# Temp_recorder_SAMD21.net
KiCad netlist of a schematic drawn in Altium Designer
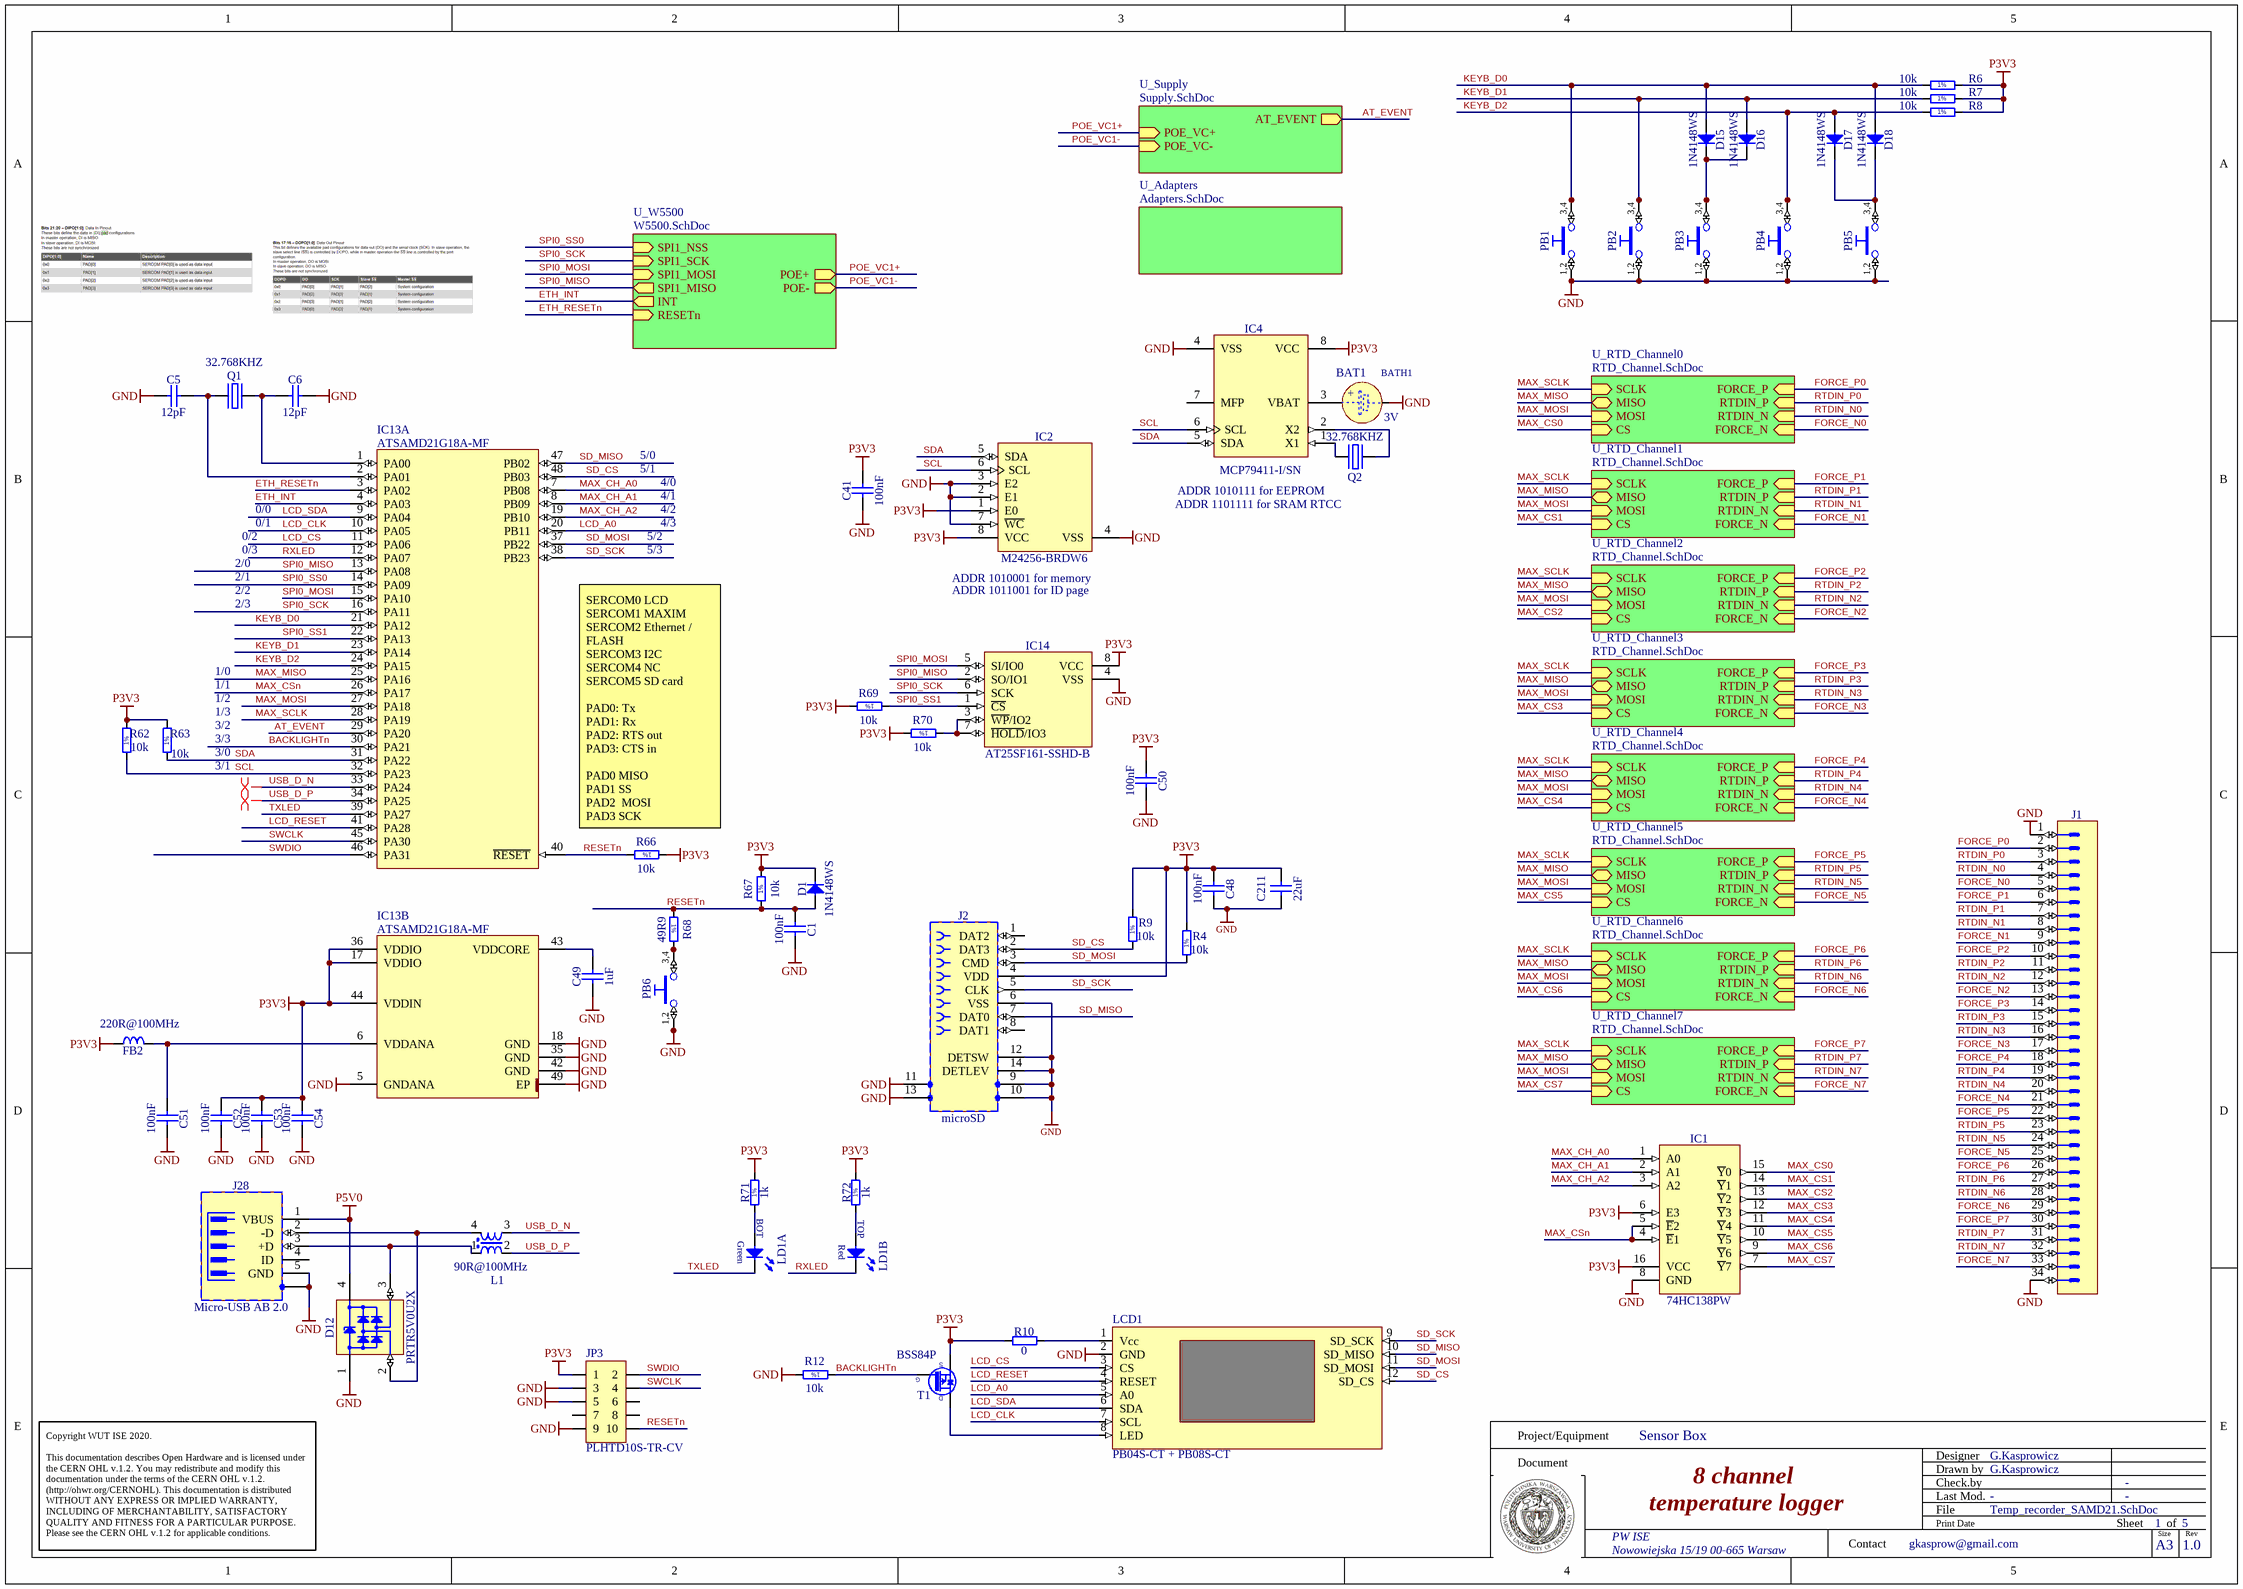
[diagram p0: Temp_recorder_SAMD21.SchDoc]

(export (version "E")
  (design (tool "Eeschema 10.0.6"))
  (components
    (comp (ref "BAT1")
      (value "3V")
      (footprint "BAT_VARTA_CR1220")
      (description "Battery for use only with Socket Holder")
      (fields
        (field (name "PART NUMBER") "BAT_VARTA_CR1220")
        (field (name "POWER") "35mAh")
        (field (name "AUTHOR") "CERN DEM JLC")
      )
      (libsource (lib "Eletro-mechanical") (part "Battery No Pin"))
    )
    (comp (ref "BATH1")
      (value "~")
      (footprint "BATH_KEYSTONE_3000")
      (description "Battery Holder whit 2 Pin")
      (fields
        (field (name "PART NUMBER") "BATH_KEYSTONE_3000")
        (field (name "MANUFACTURER") "KEYSTONE")
        (field (name "AUTHOR") "CERN DEM JLC")
      )
      (libsource (lib "Eletro-mechanical") (part "Battery Holder 2 Pin"))
    )
    (comp (ref "C1")
      (value "100nF")
      (footprint "CAPC1005X55N")
      (description "Non-polarised capacitor")
      (fields
        (field (name "PART NUMBER") "CC0402_100NF_16V_10%_X7R")
        (field (name "VOLTAGE") "16V")
        (field (name "AUTHOR") "CERN DEM JLC")
      )
      (libsource (lib "Capacitors") (part "Capacitor - non polarized"))
    )
    (comp (ref "C5")
      (value "12pF")
      (footprint "CAPC1005X55N")
      (description "Non-polarised capacitor")
      (fields
        (field (name "PART NUMBER") "CC0402_12PF_50V_5%_C0G")
        (field (name "VOLTAGE") "50V")
        (field (name "AUTHOR") "CERN DEM JLC")
      )
      (libsource (lib "Capacitors") (part "Capacitor - non polarized"))
    )
    (comp (ref "C6")
      (value "12pF")
      (footprint "CAPC1005X55N")
      (description "Non-polarised capacitor")
      (fields
        (field (name "PART NUMBER") "CC0402_12PF_50V_5%_C0G")
        (field (name "VOLTAGE") "50V")
        (field (name "AUTHOR") "CERN DEM JLC")
      )
      (libsource (lib "Capacitors") (part "Capacitor - non polarized"))
    )
    (comp (ref "C41")
      (value "100nF")
      (footprint "CAPC1005X55N")
      (description "Non-polarised capacitor")
      (fields
        (field (name "PART NUMBER") "CC0402_100NF_16V_10%_X5R")
        (field (name "VOLTAGE") "16V")
        (field (name "AUTHOR") "CERN DEM JLC")
      )
      (libsource (lib "Capacitors") (part "Capacitor - non polarized"))
    )
    (comp (ref "C48")
      (value "100nF")
      (footprint "CAPC1005X55N")
      (description "Non-polarised capacitor")
      (fields
        (field (name "PART NUMBER") "CC0402_100NF_16V_10%_X7R")
        (field (name "VOLTAGE") "16V")
        (field (name "AUTHOR") "CERN DEM JLC")
      )
      (libsource (lib "Capacitors") (part "Capacitor - non polarized"))
    )
    (comp (ref "C49")
      (value "1uF")
      (footprint "CAPC1608X87N")
      (description "Non-polarised capacitor")
      (fields
        (field (name "PART NUMBER") "CC0603_1UF_16V_10%_X7R")
        (field (name "VOLTAGE") "16V")
        (field (name "AUTHOR") "CERN DEM JLC")
      )
      (libsource (lib "Capacitors") (part "Capacitor - non polarized"))
    )
    (comp (ref "C50")
      (value "100nF")
      (footprint "CAPC1005X55N")
      (description "Non-polarised capacitor")
      (fields
        (field (name "PART NUMBER") "CC0402_100NF_16V_10%_X7R")
        (field (name "VOLTAGE") "16V")
        (field (name "AUTHOR") "CERN DEM JLC")
      )
      (libsource (lib "Capacitors") (part "Capacitor - non polarized"))
    )
    (comp (ref "C51")
      (value "100nF")
      (footprint "CAPC1005X55N")
      (description "Non-polarised capacitor")
      (fields
        (field (name "PART NUMBER") "CC0402_100NF_16V_10%_X7R")
        (field (name "VOLTAGE") "16V")
        (field (name "AUTHOR") "CERN DEM JLC")
      )
      (libsource (lib "Capacitors") (part "Capacitor - non polarized"))
    )
    (comp (ref "C52")
      (value "100nF")
      (footprint "CAPC1005X55N")
      (description "Non-polarised capacitor")
      (fields
        (field (name "PART NUMBER") "CC0402_100NF_16V_10%_X7R")
        (field (name "VOLTAGE") "16V")
        (field (name "AUTHOR") "CERN DEM JLC")
      )
      (libsource (lib "Capacitors") (part "Capacitor - non polarized"))
    )
    (comp (ref "C53")
      (value "100nF")
      (footprint "CAPC1005X55N")
      (description "Non-polarised capacitor")
      (fields
        (field (name "PART NUMBER") "CC0402_100NF_16V_10%_X7R")
        (field (name "VOLTAGE") "16V")
        (field (name "AUTHOR") "CERN DEM JLC")
      )
      (libsource (lib "Capacitors") (part "Capacitor - non polarized"))
    )
    (comp (ref "C54")
      (value "100nF")
      (footprint "CAPC1005X55N")
      (description "Non-polarised capacitor")
      (fields
        (field (name "PART NUMBER") "CC0402_100NF_16V_10%_X7R")
        (field (name "VOLTAGE") "16V")
        (field (name "AUTHOR") "CERN DEM JLC")
      )
      (libsource (lib "Capacitors") (part "Capacitor - non polarized"))
    )
    (comp (ref "C211")
      (value "22uF")
      (footprint "CAPC2012X135N")
      (description "Non-polarised capacitor")
      (fields
        (field (name "PART NUMBER") "CC0805_22UF_16V_10%_X5R")
        (field (name "VOLTAGE") "16V")
        (field (name "AUTHOR") "CERN DEM JLC")
      )
      (libsource (lib "Capacitors") (part "Capacitor - non polarized"))
    )
    (comp (ref "D1")
      (value "1N4148WS")
      (footprint "SODFL2512X100N")
      (description "Diode")
      (fields
        (field (name "VOLTAGE") "75V")
        (field (name "POWER") "150mA")
        (field (name "AUTHOR") "CERN DEM JLC")
      )
      (libsource (lib "ICs And Semiconductors") (part "Diode"))
    )
    (comp (ref "D12")
      (value "PRTR5V0U2X")
      (footprint "SOT190P230X110-4N")
      (description "Ultra Low Capacitance Double Rail-to-Rail ESD Protection Diode")
      (fields
        (field (name "VOLTAGE") "5.5V")
        (field (name "MANUFACTURER") "NXP SEMICONDUCTORS")
        (field (name "AUTHOR") "CERN DEM JLC")
      )
      (libsource (lib "ICs And Semiconductors") (part "PRTR5V0U2X"))
    )
    (comp (ref "D15")
      (value "1N4148WS")
      (footprint "SODFL2512X100N")
      (description "Diode")
      (fields
        (field (name "VOLTAGE") "75V")
        (field (name "POWER") "150mA")
        (field (name "AUTHOR") "CERN DEM JLC")
      )
      (libsource (lib "ICs And Semiconductors") (part "Diode"))
    )
    (comp (ref "D16")
      (value "1N4148WS")
      (footprint "SODFL2512X100N")
      (description "Diode")
      (fields
        (field (name "VOLTAGE") "75V")
        (field (name "POWER") "150mA")
        (field (name "AUTHOR") "CERN DEM JLC")
      )
      (libsource (lib "ICs And Semiconductors") (part "Diode"))
    )
    (comp (ref "D17")
      (value "1N4148WS")
      (footprint "SODFL2512X100N")
      (description "Diode")
      (fields
        (field (name "VOLTAGE") "75V")
        (field (name "POWER") "150mA")
        (field (name "AUTHOR") "CERN DEM JLC")
      )
      (libsource (lib "ICs And Semiconductors") (part "Diode"))
    )
    (comp (ref "D18")
      (value "1N4148WS")
      (footprint "SODFL2512X100N")
      (description "Diode")
      (fields
        (field (name "VOLTAGE") "75V")
        (field (name "POWER") "150mA")
        (field (name "AUTHOR") "CERN DEM JLC")
      )
      (libsource (lib "ICs And Semiconductors") (part "Diode"))
    )
    (comp (ref "FB2")
      (value "220R@100MHz")
      (footprint "INDC2012X105N")
      (description "Inductor")
      (fields
        (field (name "PART NUMBER") "IND0805_MURATA_BLM21PG221SN1D")
        (field (name "POWER") "2A")
        (field (name "AUTHOR") "CERN DEM JLC")
      )
      (libsource (lib "Inductors & Transformers") (part "Inductor"))
    )
    (comp (ref "IC1")
      (value "74HC138PW")
      (footprint "SOP65P640X110-16N")
      (description "3-Line to 8-Line Decoder/Demultiplexer")
      (fields (field (name "MANUFACTURER") "NXP SEMICONDUCTORS") (field (name "AUTHOR") "CERN DEM JLC"))
      (libsource (lib "ICs And Semiconductors") (part "74138_a"))
    )
    (comp (ref "IC2")
      (value "M24256-BRDW6")
      (footprint "SOP65P640X120-8N")
      (description "256-Kbit Serial I²C Bus EEPROM")
      (fields
        (field (name "PART NUMBER") "M24256-BRDW6P")
        (field (name "MANUFACTURER") "ST MICROELECTRONICS")
        (field (name "AUTHOR") "CERN DEM MR")
      )
      (libsource (lib "LIBRARY_SCH") (part "MEM_M24256-BRDW6P"))
    )
    (comp (ref "IC4")
      (value "MCP79411-I/SN")
      (footprint "SOIC127P600X175-8N")
      (description "I2C Real-Time Clock/Calendar with EEPROM, SRAM, Unique ID and Battery Switchover")
      (fields (field (name "MANUFACTURER") "MICROCHIP TECHNOLOGY") (field (name "AUTHOR") "GK"))
      (libsource (lib "ICs_Analog_Interfaces") (part "RTC_MCP79411"))
    )
    (comp (ref "IC13")
      (value "ATSAMD21G18A-MF")
      (footprint "QFN50P700X700X100-49N-S525")
      (fields (field (name "MANUFACTURER") "MICROCHIP") (field (name "AUTHOR") "CERN DEM BC"))
      (libsource (lib "ICs And Semiconductors") (part "ATSAMD21G18A-MF"))
    )
    (comp (ref "IC14")
      (value "AT25SF161-SSHD-B")
      (footprint "SOIC127P790X216-8N")
      (description "16Mb, 3V, Multiple I/O Serial NOR Flash Memory")
      (fields (field (name "AUTHOR") "GK"))
      (libsource (lib "LIBRARY_SCH") (part "MEM_AT25SF161"))
    )
    (comp (ref "J1")
      (value "Header 34")
      (footprint "3M_N2534-5002RB")
      (description "Connector 34 Male")
      (fields
        (field (name "PART NUMBER") "3M_N2534-5002RB")
        (field (name "MANUFACTURER") "3M")
        (field (name "AUTHOR") "CERN DEM JLC")
      )
      (libsource (lib "Connectors") (part "Connector 34 Male"))
    )
    (comp (ref "J2")
      (value "microSD")
      (footprint "MOLEX_502570-0893")
      (description "Connector MicroSD 8 Pin")
      (fields
        (field (name "PART NUMBER") "MOLEX_502570-0893")
        (field (name "MANUFACTURER") "MOLEX")
        (field (name "AUTHOR") "CERN DEM JLC")
      )
      (libsource (lib "Connectors") (part "MOLEX_502570-0893"))
    )
    (comp (ref "J28")
      (value "Micro-USB AB 2.0")
      (footprint "HIROSE_ZX62RD-AB-5P8(30)")
      (description "5 Pin + 1 Shield USB Receptacle")
      (fields
        (field (name "PART NUMBER") "HIROSE_ZX62RD-AB-5P8(30)")
        (field (name "MANUFACTURER") "HIROSE (HRS)")
        (field (name "AUTHOR") "CERN DEM JMW")
      )
      (libsource (lib "Connectors") (part "Connector USB 5 Pin + 1Shield"))
    )
    (comp (ref "JP3")
      (value "PLHTD10S-TR-CV")
      (footprint "PLHTD10S-TR-CV")
      (description "1.27 mm dual row goldpin (Maritex)")
      (libsource (lib "LIBRARY_SCH") (part "CON_2x5 1.27 SMT Male"))
    )
    (comp (ref "L1")
      (value "90R@100MHz")
      (footprint "IND_MURATA_DLW21S")
      (description "Inductor Common Mode")
      (fields
        (field (name "PART NUMBER") "IND_MURATA_DLW21SN900SQ2L")
        (field (name "POWER") "330mA")
        (field (name "AUTHOR") "CERN DEM JLC")
      )
      (libsource (lib "Inductors & Transformers") (part "Inductor Common Mode 1Dot-2 4Dot-3"))
    )
    (comp (ref "LCD1")
      (value "PB04S-CT + PB08S-CT")
      (footprint "library-modules:1.8TFT_Connectors")
      (description "1.8\"TFT display and SD card connector")
      (libsource (lib "LEDs_Displays") (part "LCD_TFT_1.8_SD_Connectos"))
    )
    (comp (ref "LD1")
      (value "Red/Green")
      (footprint "LED_DIALIGHT_571-0112F")
      (description "2x LED  Botom Green, Top Red")
      (fields
        (field (name "PART NUMBER") "LED_DIALIGHT_571-0112F")
        (field (name "MANUFACTURER") "DIALIGHT")
        (field (name "AUTHOR") "CERN DEM JLC")
      )
      (libsource (lib "ICs And Semiconductors") (part "LED x2 G-1C2A-BOT_R-3C4A-TOP"))
    )
    (comp (ref "PB1")
      (value "Push Button")
      (footprint "PB_TYCO_FSM6JSMA")
      (description "Push-Button Switch SPDT")
      (fields
        (field (name "PART NUMBER") "PB_TYCO_FSM6JSMA")
        (field (name "MANUFACTURER") "TYCO ELECTRONICS")
        (field (name "AUTHOR") "CERN DEM JLC")
      )
      (libsource (lib "Eletro-mechanical") (part "PB SPST 12NO-34NO"))
    )
    (comp (ref "PB2")
      (value "Push Button")
      (footprint "PB_TYCO_FSM6JSMA")
      (description "Push-Button Switch SPDT")
      (fields
        (field (name "PART NUMBER") "PB_TYCO_FSM6JSMA")
        (field (name "MANUFACTURER") "TYCO ELECTRONICS")
        (field (name "AUTHOR") "CERN DEM JLC")
      )
      (libsource (lib "Eletro-mechanical") (part "PB SPST 12NO-34NO"))
    )
    (comp (ref "PB3")
      (value "Push Button")
      (footprint "PB_TYCO_FSM6JSMA")
      (description "Push-Button Switch SPDT")
      (fields
        (field (name "PART NUMBER") "PB_TYCO_FSM6JSMA")
        (field (name "MANUFACTURER") "TYCO ELECTRONICS")
        (field (name "AUTHOR") "CERN DEM JLC")
      )
      (libsource (lib "Eletro-mechanical") (part "PB SPST 12NO-34NO"))
    )
    (comp (ref "PB4")
      (value "Push Button")
      (footprint "PB_TYCO_FSM6JSMA")
      (description "Push-Button Switch SPDT")
      (fields
        (field (name "PART NUMBER") "PB_TYCO_FSM6JSMA")
        (field (name "MANUFACTURER") "TYCO ELECTRONICS")
        (field (name "AUTHOR") "CERN DEM JLC")
      )
      (libsource (lib "Eletro-mechanical") (part "PB SPST 12NO-34NO"))
    )
    (comp (ref "PB5")
      (value "Push Button")
      (footprint "PB_TYCO_FSM6JSMA")
      (description "Push-Button Switch SPDT")
      (fields
        (field (name "PART NUMBER") "PB_TYCO_FSM6JSMA")
        (field (name "MANUFACTURER") "TYCO ELECTRONICS")
        (field (name "AUTHOR") "CERN DEM JLC")
      )
      (libsource (lib "Eletro-mechanical") (part "PB SPST 12NO-34NO"))
    )
    (comp (ref "PB6")
      (value "Push Button")
      (footprint "PB_TYCO_FSM6JSMA")
      (description "Push-Button Switch SPDT")
      (fields
        (field (name "PART NUMBER") "PB_TYCO_FSM6JSMA")
        (field (name "MANUFACTURER") "TYCO ELECTRONICS")
        (field (name "AUTHOR") "CERN DEM JLC")
      )
      (libsource (lib "Eletro-mechanical") (part "PB SPST 12NO-34NO"))
    )
    (comp (ref "Q1")
      (value "32.768KHZ")
      (footprint "XTAL_ABRACON_ABS09")
      (description "Quartz Crystal")
      (fields
        (field (name "PART NUMBER") "XTAL_32.768KHZ_ABRACON_ABS09-32.768KHZ-T")
        (field (name "MANUFACTURER") "ABRACON")
        (field (name "AUTHOR") "CERN DEM JLC")
      )
      (libsource (lib "ICs And Semiconductors") (part "Quartz Crystal"))
    )
    (comp (ref "Q2")
      (value "32.768KHZ")
      (footprint "XTAL_ABRACON_ABS09")
      (description "Quartz Crystal")
      (fields
        (field (name "PART NUMBER") "XTAL_32.768KHZ_ABRACON_ABS09-32.768KHZ-T")
        (field (name "MANUFACTURER") "ABRACON")
        (field (name "AUTHOR") "CERN DEM JLC")
      )
      (libsource (lib "ICs And Semiconductors") (part "Quartz Crystal"))
    )
    (comp (ref "R4")
      (value "10k")
      (footprint "RESC1005X40N")
      (description "Resistor - 1%")
      (fields
        (field (name "PART NUMBER") "R0402_10K_1%_0.0625W_100PPM")
        (field (name "POWER") "0.0625W")
        (field (name "AUTHOR") "CERN DEM JLC")
      )
      (libsource (lib "Resistors") (part "Resistor - 1%"))
    )
    (comp (ref "R6")
      (value "10k")
      (footprint "RESC1005X40N")
      (description "Resistor - 1%")
      (fields
        (field (name "PART NUMBER") "R0402_10K_1%_0.0625W_100PPM")
        (field (name "POWER") "0.0625W")
        (field (name "AUTHOR") "CERN DEM JLC")
      )
      (libsource (lib "Resistors") (part "Resistor - 1%"))
    )
    (comp (ref "R7")
      (value "10k")
      (footprint "RESC1005X40N")
      (description "Resistor - 1%")
      (fields
        (field (name "PART NUMBER") "R0402_10K_1%_0.0625W_100PPM")
        (field (name "POWER") "0.0625W")
        (field (name "AUTHOR") "CERN DEM JLC")
      )
      (libsource (lib "Resistors") (part "Resistor - 1%"))
    )
    (comp (ref "R8")
      (value "10k")
      (footprint "RESC1005X40N")
      (description "Resistor - 1%")
      (fields
        (field (name "PART NUMBER") "R0402_10K_1%_0.0625W_100PPM")
        (field (name "POWER") "0.0625W")
        (field (name "AUTHOR") "CERN DEM JLC")
      )
      (libsource (lib "Resistors") (part "Resistor - 1%"))
    )
    (comp (ref "R9")
      (value "10k")
      (footprint "RESC1005X40N")
      (description "Resistor - 1%")
      (fields
        (field (name "PART NUMBER") "R0402_10K_1%_0.0625W_100PPM")
        (field (name "POWER") "0.0625W")
        (field (name "AUTHOR") "CERN DEM JLC")
      )
      (libsource (lib "Resistors") (part "Resistor - 1%"))
    )
    (comp (ref "R10")
      (value "0")
      (footprint "RESC1005X40N")
      (description "Resistor")
      (fields
        (field (name "PART NUMBER") "R0402_0R_JUMPER")
        (field (name "MANUFACTURER") "GENERIC")
        (field (name "AUTHOR") "CERN DEM JLC")
      )
      (libsource (lib "Resistors") (part "Resistor"))
    )
    (comp (ref "R12")
      (value "10k")
      (footprint "RESC1005X40N")
      (description "Resistor - 1%")
      (fields
        (field (name "PART NUMBER") "R0402_10K_1%_0.0625W_100PPM")
        (field (name "POWER") "0.0625W")
        (field (name "AUTHOR") "CERN DEM JLC")
      )
      (libsource (lib "Resistors") (part "Resistor - 1%"))
    )
    (comp (ref "R62")
      (value "10k")
      (footprint "RESC1005X40N")
      (description "Resistor - 1%")
      (fields
        (field (name "PART NUMBER") "R0402_10K_1%_0.0625W_100PPM")
        (field (name "POWER") "0.0625W")
        (field (name "AUTHOR") "CERN DEM JLC")
      )
      (libsource (lib "Resistors") (part "Resistor - 1%"))
    )
    (comp (ref "R63")
      (value "10k")
      (footprint "RESC1005X40N")
      (description "Resistor - 1%")
      (fields
        (field (name "PART NUMBER") "R0402_10K_1%_0.0625W_100PPM")
        (field (name "POWER") "0.0625W")
        (field (name "AUTHOR") "CERN DEM JLC")
      )
      (libsource (lib "Resistors") (part "Resistor - 1%"))
    )
    (comp (ref "R66")
      (value "10k")
      (footprint "RESC1005X40N")
      (description "Resistor - 1%")
      (fields
        (field (name "PART NUMBER") "R0402_10K_1%_0.0625W_100PPM")
        (field (name "POWER") "0.0625W")
        (field (name "AUTHOR") "CERN DEM JLC")
      )
      (libsource (lib "Resistors") (part "Resistor - 1%"))
    )
    (comp (ref "R67")
      (value "10k")
      (footprint "RESC1005X40N")
      (description "Resistor - 1%")
      (fields
        (field (name "PART NUMBER") "R0402_10K_1%_0.0625W_100PPM")
        (field (name "POWER") "0.0625W")
        (field (name "AUTHOR") "CERN DEM JLC")
      )
      (libsource (lib "Resistors") (part "Resistor - 1%"))
    )
    (comp (ref "R68")
      (value "49R9")
      (footprint "RESC1005X40N")
      (description "Resistor - 1%")
      (fields
        (field (name "PART NUMBER") "R0402_49R9_1%_0.0625W_100PPM")
        (field (name "POWER") "0.0625W")
        (field (name "AUTHOR") "CERN DEM JLC")
      )
      (libsource (lib "Resistors") (part "Resistor - 1%"))
    )
    (comp (ref "R69")
      (value "10k")
      (footprint "RESC1005X40N")
      (description "Resistor - 1%")
      (fields
        (field (name "PART NUMBER") "R0402_10K_1%_0.0625W_100PPM")
        (field (name "POWER") "0.0625W")
        (field (name "AUTHOR") "CERN DEM JLC")
      )
      (libsource (lib "Resistors") (part "Resistor - 1%"))
    )
    (comp (ref "R70")
      (value "10k")
      (footprint "RESC1005X40N")
      (description "Resistor - 1%")
      (fields
        (field (name "PART NUMBER") "R0402_10K_1%_0.0625W_100PPM")
        (field (name "POWER") "0.0625W")
        (field (name "AUTHOR") "CERN DEM JLC")
      )
      (libsource (lib "Resistors") (part "Resistor - 1%"))
    )
    (comp (ref "R71")
      (value "1k")
      (footprint "RESC1005X40N")
      (description "Resistor - 1%")
      (fields
        (field (name "PART NUMBER") "R0402_1K_1%_0.0625W_100PPM")
        (field (name "POWER") "0.0625W")
        (field (name "AUTHOR") "CERN DEM JLC")
      )
      (libsource (lib "Resistors") (part "Resistor - 1%"))
    )
    (comp (ref "R72")
      (value "1k")
      (footprint "RESC1005X40N")
      (description "Resistor - 1%")
      (fields
        (field (name "PART NUMBER") "R0402_1K_1%_0.0625W_100PPM")
        (field (name "POWER") "0.0625W")
        (field (name "AUTHOR") "CERN DEM JLC")
      )
      (libsource (lib "Resistors") (part "Resistor - 1%"))
    )
    (comp (ref "T1")
      (value "BSS84P")
      (footprint "SOT95P240X110-3N")
      (description "P-CHANNEL MOSFET WITH DIODE")
      (fields (field (name "MANUFACTURER") "INFINEON") (field (name "AUTHOR") "CERN DEM JLC"))
      (libsource (lib "ICs And Semiconductors") (part "P-MOSFET-D 1G 2S 3D"))
    )
  )
  (nets
    (net (code "1") (name "/AT_EVENT") (class "Default")
      (node (ref "IC13") (pin "29") (pinfunction "PA20_29") (pintype "bidirectional"))
    )
    (net (code "2") (name "/BACKLIGHTn") (class "Default")
      (node (ref "IC13") (pin "30") (pinfunction "PA21_30") (pintype "bidirectional"))
      (node (ref "R12") (pin "1") (pinfunction "1_1") (pintype "passive"))
      (node (ref "T1") (pin "1") (pinfunction "G_1") (pintype "passive"))
    )
    (net (code "3") (name "/ETH_INT") (class "Default")
      (node (ref "IC13") (pin "4") (pinfunction "PA03_4") (pintype "bidirectional"))
    )
    (net (code "4") (name "/ETH_RESETn") (class "Default")
      (node (ref "IC13") (pin "3") (pinfunction "PA02_3") (pintype "bidirectional"))
    )
    (net (code "5") (name "/FORCE_N0") (class "Default")
      (node (ref "J1") (pin "5") (pinfunction "5_5") (pintype "bidirectional"))
    )
    (net (code "6") (name "/FORCE_N1") (class "Default")
      (node (ref "J1") (pin "9") (pinfunction "9_9") (pintype "bidirectional"))
    )
    (net (code "7") (name "/FORCE_N2") (class "Default")
      (node (ref "J1") (pin "13") (pinfunction "13_13") (pintype "bidirectional"))
    )
    (net (code "8") (name "/FORCE_N3") (class "Default")
      (node (ref "J1") (pin "17") (pinfunction "17_17") (pintype "bidirectional"))
    )
    (net (code "9") (name "/FORCE_N4") (class "Default")
      (node (ref "J1") (pin "21") (pinfunction "21_21") (pintype "bidirectional"))
    )
    (net (code "10") (name "/FORCE_N5") (class "Default")
      (node (ref "J1") (pin "25") (pinfunction "25_25") (pintype "bidirectional"))
    )
    (net (code "11") (name "/FORCE_N6") (class "Default")
      (node (ref "J1") (pin "29") (pinfunction "29_29") (pintype "bidirectional"))
    )
    (net (code "12") (name "/FORCE_N7") (class "Default")
      (node (ref "J1") (pin "33") (pinfunction "33_33") (pintype "bidirectional"))
    )
    (net (code "13") (name "/FORCE_P0") (class "Default")
      (node (ref "J1") (pin "2") (pinfunction "2_2") (pintype "bidirectional"))
    )
    (net (code "14") (name "/FORCE_P1") (class "Default")
      (node (ref "J1") (pin "6") (pinfunction "6_6") (pintype "bidirectional"))
    )
    (net (code "15") (name "/FORCE_P2") (class "Default")
      (node (ref "J1") (pin "10") (pinfunction "10_10") (pintype "bidirectional"))
    )
    (net (code "16") (name "/FORCE_P3") (class "Default")
      (node (ref "J1") (pin "14") (pinfunction "14_14") (pintype "bidirectional"))
    )
    (net (code "17") (name "/FORCE_P4") (class "Default")
      (node (ref "J1") (pin "18") (pinfunction "18_18") (pintype "bidirectional"))
    )
    (net (code "18") (name "/FORCE_P5") (class "Default")
      (node (ref "J1") (pin "22") (pinfunction "22_22") (pintype "bidirectional"))
    )
    (net (code "19") (name "/FORCE_P6") (class "Default")
      (node (ref "J1") (pin "26") (pinfunction "26_26") (pintype "bidirectional"))
    )
    (net (code "20") (name "/FORCE_P7") (class "Default")
      (node (ref "J1") (pin "30") (pinfunction "30_30") (pintype "bidirectional"))
    )
    (net (code "21") (name "/KEYB_D0") (class "Default")
      (node (ref "D15") (pin "2") (pinfunction "A_2") (pintype "passive"))
      (node (ref "D18") (pin "2") (pinfunction "A_2") (pintype "passive"))
      (node (ref "IC13") (pin "21") (pinfunction "PA12_21") (pintype "bidirectional"))
      (node (ref "PB1") (pin "3") (pinfunction "3_3") (pintype "bidirectional"))
      (node (ref "PB1") (pin "4") (pinfunction "4_4") (pintype "bidirectional"))
      (node (ref "R6") (pin "1") (pinfunction "1_1") (pintype "passive"))
    )
    (net (code "22") (name "/KEYB_D1") (class "Default")
      (node (ref "D16") (pin "2") (pinfunction "A_2") (pintype "passive"))
      (node (ref "IC13") (pin "23") (pinfunction "PA14_23") (pintype "bidirectional"))
      (node (ref "PB2") (pin "3") (pinfunction "3_3") (pintype "bidirectional"))
      (node (ref "PB2") (pin "4") (pinfunction "4_4") (pintype "bidirectional"))
      (node (ref "R7") (pin "1") (pinfunction "1_1") (pintype "passive"))
    )
    (net (code "23") (name "/KEYB_D2") (class "Default")
      (node (ref "D17") (pin "2") (pinfunction "A_2") (pintype "passive"))
      (node (ref "IC13") (pin "24") (pinfunction "PA15_24") (pintype "bidirectional"))
      (node (ref "PB4") (pin "3") (pinfunction "3_3") (pintype "bidirectional"))
      (node (ref "PB4") (pin "4") (pinfunction "4_4") (pintype "bidirectional"))
      (node (ref "R8") (pin "1") (pinfunction "1_1") (pintype "passive"))
    )
    (net (code "24") (name "/LCD_A0") (class "Default")
      (node (ref "IC13") (pin "20") (pinfunction "PB11_20") (pintype "bidirectional"))
      (node (ref "LCD1") (pin "5") (pinfunction "A0_5") (pintype "input"))
    )
    (net (code "25") (name "/LCD_CLK") (class "Default")
      (node (ref "IC13") (pin "10") (pinfunction "PA05_10") (pintype "bidirectional"))
      (node (ref "LCD1") (pin "7") (pinfunction "SCL_7") (pintype "input"))
    )
    (net (code "26") (name "/LCD_CS") (class "Default")
      (node (ref "IC13") (pin "11") (pinfunction "PA06_11") (pintype "bidirectional"))
      (node (ref "LCD1") (pin "3") (pinfunction "CS_3") (pintype "input"))
    )
    (net (code "27") (name "/LCD_RESET") (class "Default")
      (node (ref "IC13") (pin "41") (pinfunction "PA28_41") (pintype "bidirectional"))
      (node (ref "LCD1") (pin "4") (pinfunction "RESET_4") (pintype "input"))
    )
    (net (code "28") (name "/LCD_SDA") (class "Default")
      (node (ref "IC13") (pin "9") (pinfunction "PA04_9") (pintype "bidirectional"))
      (node (ref "LCD1") (pin "6") (pinfunction "SDA_6") (pintype "bidirectional"))
    )
    (net (code "29") (name "/MAX_CH_A0") (class "Default")
      (node (ref "IC1") (pin "1") (pinfunction "A0_1") (pintype "input"))
      (node (ref "IC13") (pin "7") (pinfunction "PB08_7") (pintype "bidirectional"))
    )
    (net (code "30") (name "/MAX_CH_A1") (class "Default")
      (node (ref "IC1") (pin "2") (pinfunction "A1_2") (pintype "input"))
      (node (ref "IC13") (pin "8") (pinfunction "PB09_8") (pintype "bidirectional"))
    )
    (net (code "31") (name "/MAX_CH_A2") (class "Default")
      (node (ref "IC1") (pin "3") (pinfunction "A2_3") (pintype "input"))
      (node (ref "IC13") (pin "19") (pinfunction "PB10_19") (pintype "bidirectional"))
    )
    (net (code "32") (name "/MAX_CS0") (class "Default")
      (node (ref "IC1") (pin "15") (pinfunction "~{Y}0_15") (pintype "output"))
    )
    (net (code "33") (name "/MAX_CS1") (class "Default")
      (node (ref "IC1") (pin "14") (pinfunction "~{Y}1_14") (pintype "output"))
    )
    (net (code "34") (name "/MAX_CS2") (class "Default")
      (node (ref "IC1") (pin "13") (pinfunction "~{Y}2_13") (pintype "output"))
    )
    (net (code "35") (name "/MAX_CS3") (class "Default")
      (node (ref "IC1") (pin "12") (pinfunction "~{Y}3_12") (pintype "output"))
    )
    (net (code "36") (name "/MAX_CS4") (class "Default")
      (node (ref "IC1") (pin "11") (pinfunction "~{Y}4_11") (pintype "output"))
    )
    (net (code "37") (name "/MAX_CS5") (class "Default")
      (node (ref "IC1") (pin "10") (pinfunction "~{Y}5_10") (pintype "output"))
    )
    (net (code "38") (name "/MAX_CS6") (class "Default")
      (node (ref "IC1") (pin "9") (pinfunction "~{Y}6_9") (pintype "output"))
    )
    (net (code "39") (name "/MAX_CS7") (class "Default")
      (node (ref "IC1") (pin "7") (pinfunction "~{Y}7_7") (pintype "output"))
    )
    (net (code "40") (name "/MAX_CSn") (class "Default")
      (node (ref "IC1") (pin "4") (pinfunction "~{E}1_4") (pintype "input"))
      (node (ref "IC1") (pin "5") (pinfunction "~{E}2_5") (pintype "input"))
      (node (ref "IC13") (pin "26") (pinfunction "PA17_26") (pintype "bidirectional"))
    )
    (net (code "41") (name "/MAX_MISO") (class "Default")
      (node (ref "IC13") (pin "25") (pinfunction "PA16_25") (pintype "bidirectional"))
    )
    (net (code "42") (name "/MAX_MOSI") (class "Default")
      (node (ref "IC13") (pin "27") (pinfunction "PA18_27") (pintype "bidirectional"))
    )
    (net (code "43") (name "/MAX_SCLK") (class "Default")
      (node (ref "IC13") (pin "28") (pinfunction "PA19_28") (pintype "bidirectional"))
    )
    (net (code "46") (name "/RESETn") (class "Default")
      (node (ref "C1") (pin "1") (pinfunction "1_1") (pintype "passive"))
      (node (ref "D1") (pin "2") (pinfunction "A_2") (pintype "passive"))
      (node (ref "IC13") (pin "40") (pinfunction "~{RESET}_40") (pintype "input"))
      (node (ref "JP3") (pin "10") (pinfunction "10_10") (pintype "passive"))
      (node (ref "R66") (pin "2") (pinfunction "2_2") (pintype "passive"))
      (node (ref "R67") (pin "1") (pinfunction "1_1") (pintype "passive"))
      (node (ref "R68") (pin "1") (pinfunction "1_1") (pintype "passive"))
    )
    (net (code "47") (name "/RTDIN_N0") (class "Default")
      (node (ref "J1") (pin "4") (pinfunction "4_4") (pintype "bidirectional"))
    )
    (net (code "48") (name "/RTDIN_N1") (class "Default")
      (node (ref "J1") (pin "8") (pinfunction "8_8") (pintype "bidirectional"))
    )
    (net (code "49") (name "/RTDIN_N2") (class "Default")
      (node (ref "J1") (pin "12") (pinfunction "12_12") (pintype "bidirectional"))
    )
    (net (code "50") (name "/RTDIN_N3") (class "Default")
      (node (ref "J1") (pin "16") (pinfunction "16_16") (pintype "bidirectional"))
    )
    (net (code "51") (name "/RTDIN_N4") (class "Default")
      (node (ref "J1") (pin "20") (pinfunction "20_20") (pintype "bidirectional"))
    )
    (net (code "52") (name "/RTDIN_N5") (class "Default")
      (node (ref "J1") (pin "24") (pinfunction "24_24") (pintype "bidirectional"))
    )
    (net (code "53") (name "/RTDIN_N6") (class "Default")
      (node (ref "J1") (pin "28") (pinfunction "28_28") (pintype "bidirectional"))
    )
    (net (code "54") (name "/RTDIN_N7") (class "Default")
      (node (ref "J1") (pin "32") (pinfunction "32_32") (pintype "bidirectional"))
    )
    (net (code "55") (name "/RTDIN_P0") (class "Default")
      (node (ref "J1") (pin "3") (pinfunction "3_3") (pintype "bidirectional"))
    )
    (net (code "56") (name "/RTDIN_P1") (class "Default")
      (node (ref "J1") (pin "7") (pinfunction "7_7") (pintype "bidirectional"))
    )
    (net (code "57") (name "/RTDIN_P2") (class "Default")
      (node (ref "J1") (pin "11") (pinfunction "11_11") (pintype "bidirectional"))
    )
    (net (code "58") (name "/RTDIN_P3") (class "Default")
      (node (ref "J1") (pin "15") (pinfunction "15_15") (pintype "bidirectional"))
    )
    (net (code "59") (name "/RTDIN_P4") (class "Default")
      (node (ref "J1") (pin "19") (pinfunction "19_19") (pintype "bidirectional"))
    )
    (net (code "60") (name "/RTDIN_P5") (class "Default")
      (node (ref "J1") (pin "23") (pinfunction "23_23") (pintype "bidirectional"))
    )
    (net (code "61") (name "/RTDIN_P6") (class "Default")
      (node (ref "J1") (pin "27") (pinfunction "27_27") (pintype "bidirectional"))
    )
    (net (code "62") (name "/RTDIN_P7") (class "Default")
      (node (ref "J1") (pin "31") (pinfunction "31_31") (pintype "bidirectional"))
    )
    (net (code "63") (name "/RXLED") (class "Default")
      (node (ref "IC13") (pin "12") (pinfunction "PA07_12") (pintype "bidirectional"))
      (node (ref "LD1") (pin "3") (pinfunction "C_3") (pintype "passive"))
    )
    (net (code "64") (name "/SCL") (class "Default")
      (node (ref "IC13") (pin "32") (pinfunction "PA23_32") (pintype "bidirectional"))
      (node (ref "IC2") (pin "6") (pinfunction "SCL_6") (pintype "input"))
      (node (ref "IC4") (pin "6") (pinfunction "SCL_6") (pintype "input"))
      (node (ref "R62") (pin "1") (pinfunction "1_1") (pintype "passive"))
    )
    (net (code "65") (name "/SDA") (class "Default")
      (node (ref "IC13") (pin "31") (pinfunction "PA22_31") (pintype "bidirectional"))
      (node (ref "IC2") (pin "5") (pinfunction "SDA_5") (pintype "bidirectional"))
      (node (ref "IC4") (pin "5") (pinfunction "SDA_5") (pintype "bidirectional"))
      (node (ref "R63") (pin "1") (pinfunction "1_1") (pintype "passive"))
    )
    (net (code "66") (name "/SD_CS") (class "Default")
      (node (ref "IC13") (pin "48") (pinfunction "PB03_48") (pintype "bidirectional"))
      (node (ref "J2") (pin "2") (pinfunction "DAT3_2") (pintype "bidirectional"))
      (node (ref "LCD1") (pin "12") (pinfunction "SD_CS_12") (pintype "input"))
      (node (ref "R9") (pin "1") (pinfunction "1_1") (pintype "passive"))
    )
    (net (code "67") (name "/SD_MISO") (class "Default")
      (node (ref "IC13") (pin "47") (pinfunction "PB02_47") (pintype "bidirectional"))
      (node (ref "J2") (pin "7") (pinfunction "DAT0_7") (pintype "bidirectional"))
      (node (ref "LCD1") (pin "10") (pinfunction "SD_MISO_10") (pintype "input"))
    )
    (net (code "68") (name "/SD_MOSI") (class "Default")
      (node (ref "IC13") (pin "37") (pinfunction "PB22_37") (pintype "bidirectional"))
      (node (ref "J2") (pin "3") (pinfunction "CMD_3") (pintype "bidirectional"))
      (node (ref "LCD1") (pin "11") (pinfunction "SD_MOSI_11") (pintype "input"))
      (node (ref "R4") (pin "1") (pinfunction "1_1") (pintype "passive"))
    )
    (net (code "69") (name "/SD_SCK") (class "Default")
      (node (ref "IC13") (pin "38") (pinfunction "PB23_38") (pintype "bidirectional"))
      (node (ref "J2") (pin "5") (pinfunction "CLK_5") (pintype "output"))
      (node (ref "LCD1") (pin "9") (pinfunction "SD_SCK_9") (pintype "input"))
    )
    (net (code "70") (name "/SPI0_MISO") (class "Default")
      (node (ref "IC13") (pin "13") (pinfunction "PA08_13") (pintype "bidirectional"))
      (node (ref "IC14") (pin "2") (pinfunction "SO/IO1_2") (pintype "bidirectional"))
    )
    (net (code "71") (name "/SPI0_MOSI") (class "Default")
      (node (ref "IC13") (pin "15") (pinfunction "PA10_15") (pintype "bidirectional"))
      (node (ref "IC14") (pin "5") (pinfunction "SI/IO0_5") (pintype "bidirectional"))
    )
    (net (code "72") (name "/SPI0_SCK") (class "Default")
      (node (ref "IC13") (pin "16") (pinfunction "PA11_16") (pintype "bidirectional"))
      (node (ref "IC14") (pin "6") (pinfunction "SCK_6") (pintype "input"))
    )
    (net (code "73") (name "/SPI0_SS0") (class "Default")
      (node (ref "IC13") (pin "14") (pinfunction "PA09_14") (pintype "bidirectional"))
    )
    (net (code "74") (name "/SPI0_SS1") (class "Default")
      (node (ref "IC13") (pin "22") (pinfunction "PA13_22") (pintype "bidirectional"))
      (node (ref "IC14") (pin "1") (pinfunction "~{CS}_1") (pintype "input"))
      (node (ref "R69") (pin "1") (pinfunction "1_1") (pintype "passive"))
    )
    (net (code "75") (name "/SWCLK") (class "Default")
      (node (ref "IC13") (pin "45") (pinfunction "PA30_45") (pintype "bidirectional"))
      (node (ref "JP3") (pin "4") (pinfunction "4_4") (pintype "passive"))
    )
    (net (code "76") (name "/SWDIO") (class "Default")
      (node (ref "IC13") (pin "46") (pinfunction "PA31_46") (pintype "bidirectional"))
      (node (ref "JP3") (pin "2") (pinfunction "2_2") (pintype "passive"))
    )
    (net (code "77") (name "/TXLED") (class "Default")
      (node (ref "IC13") (pin "39") (pinfunction "PA27_39") (pintype "bidirectional"))
      (node (ref "LD1") (pin "1") (pinfunction "C_1") (pintype "passive"))
    )
    (net (code "78") (name "/USB_D_N") (class "Default")
      (node (ref "IC13") (pin "33") (pinfunction "PA24_33") (pintype "bidirectional"))
      (node (ref "L1") (pin "3") (pinfunction "3_3") (pintype "passive"))
    )
    (net (code "79") (name "/USB_D_P") (class "Default")
      (node (ref "IC13") (pin "34") (pinfunction "PA25_34") (pintype "bidirectional"))
      (node (ref "L1") (pin "2") (pinfunction "2_2") (pintype "passive"))
    )
    (net (code "80") (name "GND") (class "Default")
      (node (ref "BATH1") (pin "2") (pinfunction "MINUS_2") (pintype "power_in"))
      (node (ref "C1") (pin "2") (pinfunction "2_2") (pintype "passive"))
      (node (ref "C211") (pin "1") (pinfunction "1_1") (pintype "passive"))
      (node (ref "C41") (pin "1") (pinfunction "1_1") (pintype "passive"))
      (node (ref "C48") (pin "2") (pinfunction "2_2") (pintype "passive"))
      (node (ref "C49") (pin "1") (pinfunction "1_1") (pintype "passive"))
      (node (ref "C5") (pin "1") (pinfunction "1_1") (pintype "passive"))
      (node (ref "C50") (pin "2") (pinfunction "2_2") (pintype "passive"))
      (node (ref "C51") (pin "2") (pinfunction "2_2") (pintype "passive"))
      (node (ref "C52") (pin "2") (pinfunction "2_2") (pintype "passive"))
      (node (ref "C53") (pin "2") (pinfunction "2_2") (pintype "passive"))
      (node (ref "C54") (pin "2") (pinfunction "2_2") (pintype "passive"))
      (node (ref "C6") (pin "2") (pinfunction "2_2") (pintype "passive"))
      (node (ref "D12") (pin "1") (pinfunction "GND_1") (pintype "power_in"))
      (node (ref "IC1") (pin "8") (pinfunction "GND_8") (pintype "power_in"))
      (node (ref "IC13") (pin "18") (pinfunction "GND_18") (pintype "power_in"))
      (node (ref "IC13") (pin "35") (pinfunction "GND_35") (pintype "power_in"))
      (node (ref "IC13") (pin "42") (pinfunction "GND_42") (pintype "power_in"))
      (node (ref "IC13") (pin "49") (pinfunction "EP_49") (pintype "passive"))
      (node (ref "IC13") (pin "5") (pinfunction "GNDANA_5") (pintype "power_in"))
      (node (ref "IC14") (pin "4") (pinfunction "VSS_4") (pintype "power_in"))
      (node (ref "IC2") (pin "2") (pinfunction "E1_2") (pintype "input"))
      (node (ref "IC2") (pin "3") (pinfunction "E2_3") (pintype "input"))
      (node (ref "IC2") (pin "4") (pinfunction "VSS_4") (pintype "power_in"))
      (node (ref "IC2") (pin "7") (pinfunction "~{WC}_7") (pintype "input"))
      (node (ref "IC4") (pin "4") (pinfunction "VSS_4") (pintype "power_in"))
      (node (ref "J1") (pin "1") (pinfunction "1_1") (pintype "bidirectional"))
      (node (ref "J1") (pin "34") (pinfunction "34_34") (pintype "bidirectional"))
      (node (ref "J2") (pin "10") (pinfunction "10_10") (pintype "passive"))
      (node (ref "J2") (pin "11") (pinfunction "11_11") (pintype "passive"))
      (node (ref "J2") (pin "12") (pinfunction "DETSW_12") (pintype "passive"))
      (node (ref "J2") (pin "13") (pinfunction "13_13") (pintype "passive"))
      (node (ref "J2") (pin "14") (pinfunction "DETLEV_14") (pintype "passive"))
      (node (ref "J2") (pin "6") (pinfunction "VSS_6") (pintype "power_in"))
      (node (ref "J2") (pin "9") (pinfunction "9_9") (pintype "passive"))
      (node (ref "J28") (pin "5") (pinfunction "GND_5") (pintype "power_in"))
      (node (ref "J28") (pin "6") (pinfunction "SH_6") (pintype "power_in"))
      (node (ref "JP3") (pin "3") (pinfunction "3_3") (pintype "passive"))
      (node (ref "JP3") (pin "5") (pinfunction "5_5") (pintype "passive"))
      (node (ref "JP3") (pin "9") (pinfunction "9_9") (pintype "passive"))
      (node (ref "LCD1") (pin "2") (pinfunction "GND_2") (pintype "power_in"))
      (node (ref "PB1") (pin "1") (pinfunction "1_1") (pintype "bidirectional"))
      (node (ref "PB1") (pin "2") (pinfunction "2_2") (pintype "bidirectional"))
      (node (ref "PB2") (pin "1") (pinfunction "1_1") (pintype "bidirectional"))
      (node (ref "PB2") (pin "2") (pinfunction "2_2") (pintype "bidirectional"))
      (node (ref "PB3") (pin "1") (pinfunction "1_1") (pintype "bidirectional"))
      (node (ref "PB3") (pin "2") (pinfunction "2_2") (pintype "bidirectional"))
      (node (ref "PB4") (pin "1") (pinfunction "1_1") (pintype "bidirectional"))
      (node (ref "PB4") (pin "2") (pinfunction "2_2") (pintype "bidirectional"))
      (node (ref "PB5") (pin "1") (pinfunction "1_1") (pintype "bidirectional"))
      (node (ref "PB5") (pin "2") (pinfunction "2_2") (pintype "bidirectional"))
      (node (ref "PB6") (pin "1") (pinfunction "1_1") (pintype "bidirectional"))
      (node (ref "PB6") (pin "2") (pinfunction "2_2") (pintype "bidirectional"))
      (node (ref "R12") (pin "2") (pinfunction "2_2") (pintype "passive"))
    )
    (net (code "81") (name "Net-(BATH1-PLUS)") (class "Default")
      (node (ref "BATH1") (pin "1") (pinfunction "PLUS_1") (pintype "power_in"))
      (node (ref "IC4") (pin "3") (pinfunction "VBAT_3") (pintype "power_in"))
    )
    (net (code "82") (name "Net-(D12-I{slash}O1)") (class "Default")
      (node (ref "D12") (pin "2") (pinfunction "I/O1_2") (pintype "bidirectional"))
      (node (ref "J28") (pin "2") (pinfunction "-D_2") (pintype "bidirectional"))
      (node (ref "L1") (pin "4") (pinfunction "4_4") (pintype "passive"))
    )
    (net (code "83") (name "Net-(D12-I{slash}O2)") (class "Default")
      (node (ref "D12") (pin "3") (pinfunction "I/O2_3") (pintype "bidirectional"))
      (node (ref "J28") (pin "3") (pinfunction "+D_3") (pintype "bidirectional"))
      (node (ref "L1") (pin "1") (pinfunction "1_1") (pintype "passive"))
    )
    (net (code "84") (name "Net-(D15-C)") (class "Default")
      (node (ref "D15") (pin "1") (pinfunction "C_1") (pintype "passive"))
      (node (ref "D16") (pin "1") (pinfunction "C_1") (pintype "passive"))
      (node (ref "PB3") (pin "3") (pinfunction "3_3") (pintype "bidirectional"))
      (node (ref "PB3") (pin "4") (pinfunction "4_4") (pintype "bidirectional"))
    )
    (net (code "85") (name "Net-(D17-C)") (class "Default")
      (node (ref "D17") (pin "1") (pinfunction "C_1") (pintype "passive"))
      (node (ref "D18") (pin "1") (pinfunction "C_1") (pintype "passive"))
      (node (ref "PB5") (pin "3") (pinfunction "3_3") (pintype "bidirectional"))
      (node (ref "PB5") (pin "4") (pinfunction "4_4") (pintype "bidirectional"))
    )
    (net (code "86") (name "Net-(IC4-X1)") (class "Default")
      (node (ref "IC4") (pin "1") (pinfunction "X1_1") (pintype "input"))
      (node (ref "Q2") (pin "1") (pinfunction "OSC1_1") (pintype "passive"))
    )
    (net (code "87") (name "Net-(IC4-X2)") (class "Default")
      (node (ref "IC4") (pin "2") (pinfunction "X2_2") (pintype "output"))
      (node (ref "Q2") (pin "2") (pinfunction "OSC2_2") (pintype "passive"))
    )
    (net (code "88") (name "Net-(IC13A-PA00)") (class "Default")
      (node (ref "C6") (pin "1") (pinfunction "1_1") (pintype "passive"))
      (node (ref "IC13") (pin "1") (pinfunction "PA00_1") (pintype "bidirectional"))
      (node (ref "Q1") (pin "2") (pinfunction "OSC2_2") (pintype "passive"))
    )
    (net (code "89") (name "Net-(IC13A-PA01)") (class "Default")
      (node (ref "C5") (pin "2") (pinfunction "2_2") (pintype "passive"))
      (node (ref "IC13") (pin "2") (pinfunction "PA01_2") (pintype "bidirectional"))
      (node (ref "Q1") (pin "1") (pinfunction "OSC1_1") (pintype "passive"))
    )
    (net (code "90") (name "Net-(IC13B-VDDANA)") (class "Default")
      (node (ref "C51") (pin "1") (pinfunction "1_1") (pintype "passive"))
      (node (ref "FB2") (pin "2") (pinfunction "2_2") (pintype "passive"))
      (node (ref "IC13") (pin "6") (pinfunction "VDDANA_6") (pintype "power_in"))
    )
    (net (code "91") (name "Net-(IC13B-VDDCORE)") (class "Default")
      (node (ref "C49") (pin "2") (pinfunction "2_2") (pintype "passive"))
      (node (ref "IC13") (pin "43") (pinfunction "VDDCORE_43") (pintype "power_in"))
    )
    (net (code "92") (name "Net-(IC14-~{HOLD}{slash}IO3)") (class "Default")
      (node (ref "IC14") (pin "3") (pinfunction "~{WP}/IO2_3") (pintype "bidirectional"))
      (node (ref "IC14") (pin "7") (pinfunction "~{HOLD}/IO3_7") (pintype "bidirectional"))
      (node (ref "R70") (pin "1") (pinfunction "1_1") (pintype "passive"))
    )
    (net (code "93") (name "Net-(LCD1-LED)") (class "Default")
      (node (ref "LCD1") (pin "8") (pinfunction "LED_8") (pintype "input"))
      (node (ref "T1") (pin "3") (pinfunction "D_3") (pintype "passive"))
    )
    (net (code "94") (name "Net-(LCD1-Vcc)") (class "Default")
      (node (ref "LCD1") (pin "1") (pinfunction "Vcc_1") (pintype "power_in"))
      (node (ref "R10") (pin "2") (pinfunction "2_2") (pintype "passive"))
    )
    (net (code "95") (name "Net-(LD1A-A)") (class "Default")
      (node (ref "LD1") (pin "2") (pinfunction "A_2") (pintype "passive"))
      (node (ref "R71") (pin "1") (pinfunction "1_1") (pintype "passive"))
    )
    (net (code "96") (name "Net-(LD1B-A)") (class "Default")
      (node (ref "LD1") (pin "4") (pinfunction "A_4") (pintype "passive"))
      (node (ref "R72") (pin "1") (pinfunction "1_1") (pintype "passive"))
    )
    (net (code "97") (name "Net-(PB6-Pad3)") (class "Default")
      (node (ref "PB6") (pin "3") (pinfunction "3_3") (pintype "bidirectional"))
      (node (ref "PB6") (pin "4") (pinfunction "4_4") (pintype "bidirectional"))
      (node (ref "R68") (pin "2") (pinfunction "2_2") (pintype "passive"))
    )
    (net (code "98") (name "P3V3") (class "Default")
      (node (ref "C211") (pin "2") (pinfunction "2_2") (pintype "passive"))
      (node (ref "C41") (pin "2") (pinfunction "2_2") (pintype "passive"))
      (node (ref "C48") (pin "1") (pinfunction "1_1") (pintype "passive"))
      (node (ref "C50") (pin "1") (pinfunction "1_1") (pintype "passive"))
      (node (ref "C52") (pin "1") (pinfunction "1_1") (pintype "passive"))
      (node (ref "C53") (pin "1") (pinfunction "1_1") (pintype "passive"))
      (node (ref "C54") (pin "1") (pinfunction "1_1") (pintype "passive"))
      (node (ref "D1") (pin "1") (pinfunction "C_1") (pintype "passive"))
      (node (ref "FB2") (pin "1") (pinfunction "1_1") (pintype "passive"))
      (node (ref "IC1") (pin "16") (pinfunction "VCC_16") (pintype "power_in"))
      (node (ref "IC1") (pin "6") (pinfunction "E3_6") (pintype "input"))
      (node (ref "IC13") (pin "17") (pinfunction "VDDIO_17") (pintype "power_in"))
      (node (ref "IC13") (pin "36") (pinfunction "VDDIO_36") (pintype "power_in"))
      (node (ref "IC13") (pin "44") (pinfunction "VDDIN_44") (pintype "power_in"))
      (node (ref "IC14") (pin "8") (pinfunction "VCC_8") (pintype "power_in"))
      (node (ref "IC2") (pin "1") (pinfunction "E0_1") (pintype "input"))
      (node (ref "IC2") (pin "8") (pinfunction "VCC_8") (pintype "power_in"))
      (node (ref "IC4") (pin "8") (pinfunction "VCC_8") (pintype "power_in"))
      (node (ref "J2") (pin "4") (pinfunction "VDD_4") (pintype "power_in"))
      (node (ref "JP3") (pin "1") (pinfunction "1_1") (pintype "passive"))
      (node (ref "R10") (pin "1") (pinfunction "1_1") (pintype "passive"))
      (node (ref "R4") (pin "2") (pinfunction "2_2") (pintype "passive"))
      (node (ref "R6") (pin "2") (pinfunction "2_2") (pintype "passive"))
      (node (ref "R62") (pin "2") (pinfunction "2_2") (pintype "passive"))
      (node (ref "R63") (pin "2") (pinfunction "2_2") (pintype "passive"))
      (node (ref "R66") (pin "1") (pinfunction "1_1") (pintype "passive"))
      (node (ref "R67") (pin "2") (pinfunction "2_2") (pintype "passive"))
      (node (ref "R69") (pin "2") (pinfunction "2_2") (pintype "passive"))
      (node (ref "R7") (pin "2") (pinfunction "2_2") (pintype "passive"))
      (node (ref "R70") (pin "2") (pinfunction "2_2") (pintype "passive"))
      (node (ref "R71") (pin "2") (pinfunction "2_2") (pintype "passive"))
      (node (ref "R72") (pin "2") (pinfunction "2_2") (pintype "passive"))
      (node (ref "R8") (pin "2") (pinfunction "2_2") (pintype "passive"))
      (node (ref "R9") (pin "2") (pinfunction "2_2") (pintype "passive"))
      (node (ref "T1") (pin "2") (pinfunction "S_2") (pintype "passive"))
    )
    (net (code "99") (name "P5V0") (class "Default")
      (node (ref "D12") (pin "4") (pinfunction "VCC_4") (pintype "power_in"))
      (node (ref "J28") (pin "1") (pinfunction "VBUS_1") (pintype "power_in"))
    )
    (net (code "100") (name "unconnected-(IC4-MFP-Pad7)") (class "Default")
      (node (ref "IC4") (pin "7") (pinfunction "MFP_7") (pintype "open_collector"))
    )
    (net (code "101") (name "unconnected-(J2-DAT1-Pad8)") (class "Default")
      (node (ref "J2") (pin "8") (pinfunction "DAT1_8") (pintype "bidirectional"))
    )
    (net (code "102") (name "unconnected-(J2-DAT2-Pad1)") (class "Default")
      (node (ref "J2") (pin "1") (pinfunction "DAT2_1") (pintype "bidirectional"))
    )
    (net (code "103") (name "unconnected-(J28-ID-Pad4)") (class "Default")
      (node (ref "J28") (pin "4") (pinfunction "ID_4") (pintype "passive"))
    )
    (net (code "104") (name "unconnected-(JP3-Pad6)") (class "Default")
      (node (ref "JP3") (pin "6") (pinfunction "6_6") (pintype "passive"))
    )
    (net (code "105") (name "unconnected-(JP3-Pad7)") (class "Default")
      (node (ref "JP3") (pin "7") (pinfunction "7_7") (pintype "passive"))
    )
    (net (code "106") (name "unconnected-(JP3-Pad8)") (class "Default")
      (node (ref "JP3") (pin "8") (pinfunction "8_8") (pintype "passive"))
    )
  )
)
